# 4v4_Power_Supply.net
KiCad netlist of a schematic drawn in Altium Designer
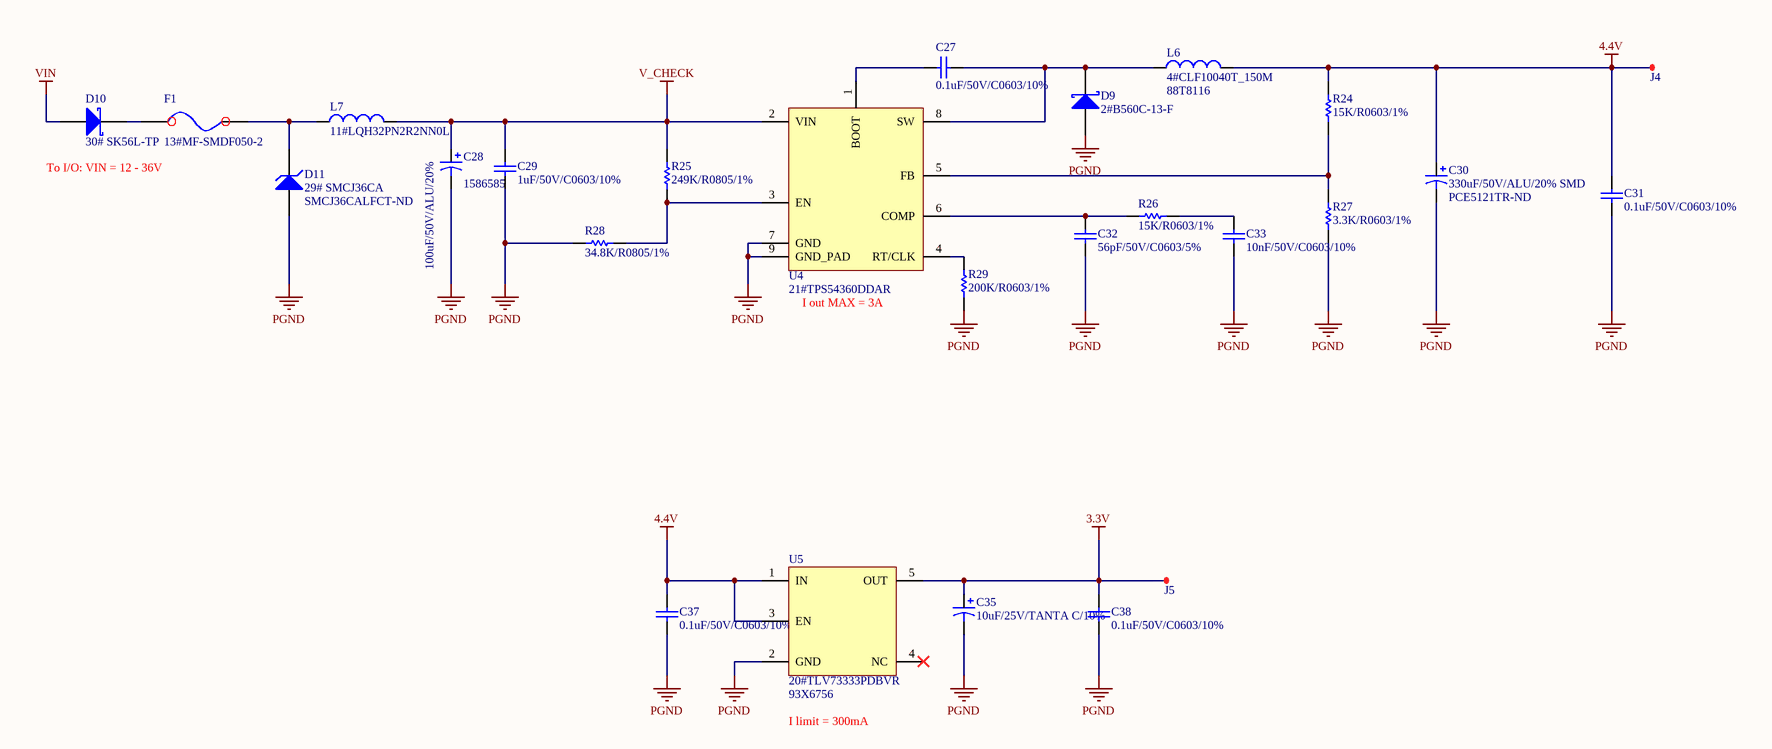
[diagram p0: 4v4 Power Supply.SchDoc]

(export (version "E")
  (design (tool "Eeschema 10.0.6"))
  (components
    (comp (ref "C27")
      (value "0.1uF/50V/C0603/10%")
      (footprint "Cap Ceramic 0603 SMD")
      (description "CAP CER 0.1UF 50V 10% X7R 0603")
      (fields
        (field (name "MANUFACTURER") "Murata Electronics North America")
        (field (name "MANUFACTURER PART NUMBER") "GRM188R71H104KA93D")
      )
      (libsource (lib "GSHT_181013") (part "0.1uF/50V/C0603/10%"))
    )
    (comp (ref "C28")
      (value "100uF/50V/ALU/20%")
      (footprint "CAP ALU CASE F SMD")
      (description "CAP ALU 100UF 20% 50V RADIAL")
      (fields
        (field (name "MANUFACTURER") "Panasonic Electronic Components")
        (field (name "MANUFACTURER PART NUMBER") "ECA-1HM101B")
        (field (name "SUPPLIER PART NUMBER 1") "1586585")
      )
      (libsource (lib "GSHT_181013") (part "100uF/50V/ALU 8X11.5/20%"))
    )
    (comp (ref "C29")
      (value "1uF/50V/C0603/10%")
      (footprint "Cap Ceramic 0603 SMD")
      (description "CAP CER 1UF 50V X7R 0603")
      (fields
        (field (name "MANUFACTURER") "Samsung Electro-Mechanics America, Inc.")
        (field (name "MANUFACTURER PART NUMBER") "CL21B105KBFNNNE")
      )
      (libsource (lib "GSHT_181013") (part "1uF/50V/C0603/10%"))
    )
    (comp (ref "C30")
      (value "330uF/50V/ALU/20% SMD")
      (footprint "CAP ALU CASE G SMD")
      (description "CAP ALU 330UF 20% 50V SMD")
      (fields
        (field (name "MANUFACTURER") "Nichicon")
        (field (name "MANUFACTURER PART NUMBER") "UPW1J331MHD")
        (field (name "SUPPLIER PART NUMBER 1") "PCE5121TR-ND")
      )
      (libsource (lib "GSHT_181013") (part "330uF/50V/ALU12.5X20mm/20%/7000Hrs"))
    )
    (comp (ref "C31")
      (value "0.1uF/50V/C0603/10%")
      (footprint "Cap Ceramic 0603 SMD")
      (description "CAP CER 0.1UF 50V 10% X7R 0603")
      (fields
        (field (name "MANUFACTURER") "Murata Electronics North America")
        (field (name "MANUFACTURER PART NUMBER") "GRM188R71H104KA93D")
      )
      (libsource (lib "GSHT_181013") (part "0.1uF/50V/C0603/10%"))
    )
    (comp (ref "C32")
      (value "56pF/50V/C0603/5%")
      (footprint "Cap Ceramic 0603 SMD")
      (description "Cap Ceramic 56pF 50V C0G 5% SMD 0603 125C Paper T/R")
      (fields
        (field (name "MANUFACTURER") "Samsung")
        (field (name "MANUFACTURER PART NUMBER") "CL10C560JB8NNNC")
      )
      (libsource (lib "GSHT_181013") (part "56pF/50V/C0603/5%"))
    )
    (comp (ref "C33")
      (value "10nF/50V/C0603/10%")
      (footprint "Cap Ceramic 0603 SMD")
      (description "CAP CER 10000PF 50V X7R 0603")
      (fields
        (field (name "MANUFACTURER") "Murata Electronics North America")
        (field (name "MANUFACTURER PART NUMBER") "GRM188R71H103KA01D")
      )
      (libsource (lib "GSHT_181013") (part "10nF/50V/C0603/10%"))
    )
    (comp (ref "C35")
      (value "10uF/25V/TANTA C/10%")
      (footprint "CAP TANT CASE C SMD")
      (description "Tantalum Capacitors - Solid SMD 25v 10uF 20%Tol Code C")
      (fields
        (field (name "MANUFACTURER") "Kyocera AVX")
        (field (name "MANUFACTURER PART NUMBER") "TAJB106M025RNJ")
      )
      (libsource (lib "GSHT_181013") (part "TAJB106M025RNJ"))
    )
    (comp (ref "C37")
      (value "0.1uF/50V/C0603/10%")
      (footprint "Cap Ceramic 0603 SMD")
      (description "CAP CER 0.1UF 50V 10% X7R 0603")
      (fields
        (field (name "MANUFACTURER") "Murata Electronics North America")
        (field (name "MANUFACTURER PART NUMBER") "GRM188R71H104KA93D")
      )
      (libsource (lib "GSHT_181013") (part "0.1uF/50V/C0603/10%"))
    )
    (comp (ref "C38")
      (value "0.1uF/50V/C0603/10%")
      (footprint "Cap Ceramic 0603 SMD")
      (description "CAP CER 0.1UF 50V 10% X7R 0603")
      (fields
        (field (name "MANUFACTURER") "Murata Electronics North America")
        (field (name "MANUFACTURER PART NUMBER") "GRM188R71H104KA93D")
      )
      (libsource (lib "GSHT_181013") (part "0.1uF/50V/C0603/10%"))
    )
    (comp (ref "D9")
      (value "2#B560C-13-F")
      (footprint "2# B560C")
      (description "DIODE SCHOTTKY 60V 5A SMC")
      (fields (field (name "MANUFACTURER") "Diodes") (field (name "MANUFACTURER PART NUMBER") "B560C-13-F"))
      (libsource (lib "GSHT_181013") (part "2#B560C-13-F"))
    )
    (comp (ref "D10")
      (value "30# SK56L-TP")
      (footprint "30# SK56L-TPMSCT-ND")
      (description "DIODE SCHOTTKY 60V 5A")
      (fields
        (field (name "MANUFACTURER") "Micro Commercial Co")
        (field (name "MANUFACTURER PART NUMBER") "SK56L-TP")
      )
      (libsource (lib "GSHT_181013") (part "30# SK56L-TP"))
    )
    (comp (ref "D11")
      (value "29# SMCJ36CA")
      (footprint "29# diode SMCJ36A")
      (description "TVS DIODE 36VWM 58.1VC SMC")
      (fields
        (field (name "MANUFACTURER") "Littelfuse")
        (field (name "MANUFACTURER PART NUMBER") "SMCJ36CA")
        (field (name "SUPPLIER PART NUMBER 1") "SMCJ36CALFCT-ND")
      )
      (libsource (lib "GSHT_181013") (part "29# SMCJ36CA"))
    )
    (comp (ref "F1")
      (value "13#MF-SMDF050-2")
      (footprint "13# MF-SMDF050")
      (description "PTC RESETTABLE .55A 60V 2018")
      (fields (field (name "MANUFACTURER") "Bourns") (field (name "MANUFACTURER PART NUMBER") "MF-SMDF050-2"))
      (libsource (lib "GSHT_181013") (part "13#MF-SMDF050-2"))
    )
    (comp (ref "J4")
      (value "TEST POINT")
      (footprint "TEST POINT 1mm")
      (description "TPoint")
      (libsource (lib "GSHT_181013") (part "PAD 1mm"))
    )
    (comp (ref "J5")
      (value "TEST POINT")
      (footprint "TEST POINT 1mm")
      (description "TPoint")
      (libsource (lib "GSHT_181013") (part "PAD 1mm"))
    )
    (comp (ref "L6")
      (value "4#CLF10040T_150M")
      (footprint "4# clf10040XX")
      (description "FIXED IND 15uH 3.2A 40 MOHM (10.0×9.7×3.8)")
      (fields (field (name "SUPPLIER PART NUMBER 1") "88T8116"))
      (libsource (lib "GSHT_181013") (part "4#CLF10040T_150M"))
    )
    (comp (ref "L7")
      (value "11#LQH32PN2R2NN0L")
      (footprint "11# LQH32PN2R2")
      (description "Inductor Power Chip Shielded Wirewound 2.2uH 30% 1MHz Ferrite 1.6A 91.2mOhm DCR 1210 Embossed T/R")
      (fields
        (field (name "MANUFACTURER") "Murata")
        (field (name "MANUFACTURER PART NUMBER") "LQH32PN2R2NN0L")
      )
      (libsource (lib "GSHT_181013") (part "11#LQH32PN2R2NN0L"))
    )
    (comp (ref "R24")
      (value "15K/R0603/1%")
      (footprint "Res 0603 SMD")
      (description "RES SMD 15K OHM 1% 1/10W 0603")
      (fields
        (field (name "MANUFACTURER") "Yageo")
        (field (name "MANUFACTURER PART NUMBER") "RC0603FR-0715KL")
      )
      (libsource (lib "GSHT_181013") (part "15K/R0603/1%"))
    )
    (comp (ref "R25")
      (value "249K/R0805/1%")
      (footprint "Res 0805 SMD")
      (description "RES SMD 249K OHM 1% 1/10W 0805")
      (fields
        (field (name "MANUFACTURER") "Yageo")
        (field (name "MANUFACTURER PART NUMBER") "RC0603FR-07249KL")
      )
      (libsource (lib "GSHT_181013") (part "249K/R0805/1%"))
    )
    (comp (ref "R26")
      (value "15K/R0603/1%")
      (footprint "Res 0603 SMD")
      (description "RES SMD 15K OHM 1% 1/10W 0603")
      (fields
        (field (name "MANUFACTURER") "Yageo")
        (field (name "MANUFACTURER PART NUMBER") "RC0603FR-0715KL")
      )
      (libsource (lib "GSHT_181013") (part "15K/R0603/1%"))
    )
    (comp (ref "R27")
      (value "3.3K/R0603/1%")
      (footprint "Cap Ceramic 0603 SMD")
      (description "RES SMD 3.3K OHM 1% 1/10W 0603")
      (fields
        (field (name "MANUFACTURER") "Yageo")
        (field (name "MANUFACTURER PART NUMBER") "RC0603FR-073K3L")
      )
      (libsource (lib "GSHT_181013") (part "3.3K/R0603/1%"))
    )
    (comp (ref "R28")
      (value "34.8K/R0805/1%")
      (footprint "Res 0805 SMD")
      (description "Thick Film Resistors - SMD 34.8K OHM 1% 0805")
      (fields
        (field (name "MANUFACTURER") "Yageo")
        (field (name "MANUFACTURER PART NUMBER") "RC0603FR-0734K8L")
      )
      (libsource (lib "GSHT_181013") (part "34.8K/R0805/1%"))
    )
    (comp (ref "R29")
      (value "200K/R0603/1%")
      (footprint "Res 0603 SMD")
      (description "RES SMD 200K OHM 1% 1/10W 0603")
      (fields
        (field (name "MANUFACTURER") "Yageo")
        (field (name "MANUFACTURER PART NUMBER") "RC0603FR-07200KL")
      )
      (libsource (lib "GSHT_181013") (part "200K/R0603/1%"))
    )
    (comp (ref "U4")
      (value "21#TPS54360DDAR")
      (footprint "21# TPS54360")
      (description "Voltage Regulators - Switching Regulators 60 Vin,3.5 A,SD DC-DC Converter")
      (fields
        (field (name "MANUFACTURER") "Texas Instruments")
        (field (name "MANUFACTURER PART NUMBER") "TPS54360DDAR")
      )
      (libsource (lib "GSHT_181013") (part "21#TPS54360DDAR"))
    )
    (comp (ref "U5")
      (value "20#TLV73333PDBVR")
      (footprint "20# TLV73333PDBVR")
      (description "LDO Regulator Pos 3.3V 0.3A 5-Pin SOT-23 T/R")
      (fields
        (field (name "MANUFACTURER") "Texas Instruments")
        (field (name "MANUFACTURER PART NUMBER") "TLV73333PDBVR")
        (field (name "SUPPLIER PART NUMBER 1") "93X6756")
      )
      (libsource (lib "GSHT_181013") (part "20#TLV73333PDBVR"))
    )
  )
  (nets
    (net (code "1") (name "3.3V") (class "Default")
      (node (ref "C35") (pin "1") (pinfunction "1_1") (pintype "passive"))
      (node (ref "C38") (pin "2") (pinfunction "2_2") (pintype "passive"))
      (node (ref "J5") (pin "1") (pinfunction "TP_1") (pintype "passive"))
      (node (ref "U5") (pin "5") (pinfunction "OUT_5") (pintype "passive"))
    )
    (net (code "2") (name "4.4V") (class "Default")
      (node (ref "C30") (pin "1") (pinfunction "1_1") (pintype "passive"))
      (node (ref "C31") (pin "2") (pinfunction "2_2") (pintype "passive"))
      (node (ref "C37") (pin "2") (pinfunction "2_2") (pintype "passive"))
      (node (ref "J4") (pin "1") (pinfunction "TP_1") (pintype "passive"))
      (node (ref "L6") (pin "2") (pinfunction "2_2") (pintype "passive"))
      (node (ref "R24") (pin "2") (pinfunction "2_2") (pintype "passive"))
      (node (ref "U5") (pin "1") (pinfunction "IN_1") (pintype "passive"))
      (node (ref "U5") (pin "3") (pinfunction "EN_3") (pintype "passive"))
    )
    (net (code "3") (name "Net-(C33-Pad2)") (class "Default")
      (node (ref "C33") (pin "2") (pinfunction "2_2") (pintype "passive"))
      (node (ref "R26") (pin "1") (pinfunction "1_1") (pintype "passive"))
    )
    (net (code "4") (name "Net-(D9-K)") (class "Default")
      (node (ref "C27") (pin "2") (pinfunction "2_2") (pintype "passive"))
      (node (ref "D9") (pin "2") (pinfunction "K_2") (pintype "passive"))
      (node (ref "L6") (pin "1") (pinfunction "1_1") (pintype "passive"))
      (node (ref "U4") (pin "8") (pinfunction "SW_8") (pintype "passive"))
    )
    (net (code "5") (name "Net-(D10-K)") (class "Default")
      (node (ref "D10") (pin "2") (pinfunction "K_2") (pintype "passive"))
      (node (ref "F1") (pin "1") (pinfunction "IN_1") (pintype "passive"))
    )
    (net (code "6") (name "Net-(D11-K)") (class "Default")
      (node (ref "D11") (pin "2") (pinfunction "K_2") (pintype "passive"))
      (node (ref "F1") (pin "2") (pinfunction "OUT_2") (pintype "passive"))
      (node (ref "L7") (pin "1") (pinfunction "1_1") (pintype "passive"))
    )
    (net (code "7") (name "Net-(U4-BOOT)") (class "Default")
      (node (ref "C27") (pin "1") (pinfunction "1_1") (pintype "passive"))
      (node (ref "U4") (pin "1") (pinfunction "BOOT_1") (pintype "passive"))
    )
    (net (code "8") (name "Net-(U4-COMP)") (class "Default")
      (node (ref "C32") (pin "2") (pinfunction "2_2") (pintype "passive"))
      (node (ref "R26") (pin "2") (pinfunction "2_2") (pintype "passive"))
      (node (ref "U4") (pin "6") (pinfunction "COMP_6") (pintype "passive"))
    )
    (net (code "9") (name "Net-(U4-EN)") (class "Default")
      (node (ref "R25") (pin "1") (pinfunction "1_1") (pintype "passive"))
      (node (ref "R28") (pin "2") (pinfunction "2_2") (pintype "passive"))
      (node (ref "U4") (pin "3") (pinfunction "EN_3") (pintype "passive"))
    )
    (net (code "10") (name "Net-(U4-FB)") (class "Default")
      (node (ref "R24") (pin "1") (pinfunction "1_1") (pintype "passive"))
      (node (ref "R27") (pin "2") (pinfunction "2_2") (pintype "passive"))
      (node (ref "U4") (pin "5") (pinfunction "FB_5") (pintype "passive"))
    )
    (net (code "11") (name "Net-(U4-RT{slash}CLK)") (class "Default")
      (node (ref "R29") (pin "1") (pinfunction "1_1") (pintype "passive"))
      (node (ref "U4") (pin "4") (pinfunction "RT/CLK_4") (pintype "passive"))
    )
    (net (code "12") (name "PGND") (class "Default")
      (node (ref "C28") (pin "2") (pinfunction "2_2") (pintype "passive"))
      (node (ref "C29") (pin "1") (pinfunction "1_1") (pintype "passive"))
      (node (ref "C30") (pin "2") (pinfunction "2_2") (pintype "passive"))
      (node (ref "C31") (pin "1") (pinfunction "1_1") (pintype "passive"))
      (node (ref "C32") (pin "1") (pinfunction "1_1") (pintype "passive"))
      (node (ref "C33") (pin "1") (pinfunction "1_1") (pintype "passive"))
      (node (ref "C35") (pin "2") (pinfunction "2_2") (pintype "passive"))
      (node (ref "C37") (pin "1") (pinfunction "1_1") (pintype "passive"))
      (node (ref "C38") (pin "1") (pinfunction "1_1") (pintype "passive"))
      (node (ref "D11") (pin "1") (pinfunction "A_1") (pintype "passive"))
      (node (ref "D9") (pin "1") (pinfunction "A_1") (pintype "passive"))
      (node (ref "R27") (pin "1") (pinfunction "1_1") (pintype "passive"))
      (node (ref "R28") (pin "1") (pinfunction "1_1") (pintype "passive"))
      (node (ref "R29") (pin "2") (pinfunction "2_2") (pintype "passive"))
      (node (ref "U4") (pin "7") (pinfunction "GND_7") (pintype "passive"))
      (node (ref "U4") (pin "9") (pinfunction "GND_PAD_9") (pintype "passive"))
      (node (ref "U5") (pin "2") (pinfunction "GND_2") (pintype "passive"))
    )
    (net (code "13") (name "VIN") (class "Default")
      (node (ref "D10") (pin "1") (pinfunction "A_1") (pintype "passive"))
    )
    (net (code "14") (name "V_CHECK") (class "Default")
      (node (ref "C28") (pin "1") (pinfunction "1_1") (pintype "passive"))
      (node (ref "C29") (pin "2") (pinfunction "2_2") (pintype "passive"))
      (node (ref "L7") (pin "2") (pinfunction "2_2") (pintype "passive"))
      (node (ref "R25") (pin "2") (pinfunction "2_2") (pintype "passive"))
      (node (ref "U4") (pin "2") (pinfunction "VIN_2") (pintype "passive"))
    )
    (net (code "15") (name "unconnected-(U5-NC-Pad4)") (class "Default")
      (node (ref "U5") (pin "4") (pinfunction "NC_4") (pintype "passive+no_connect"))
    )
  )
)
